# groundControl.net
KiCad netlist of a schematic drawn in EAGLE
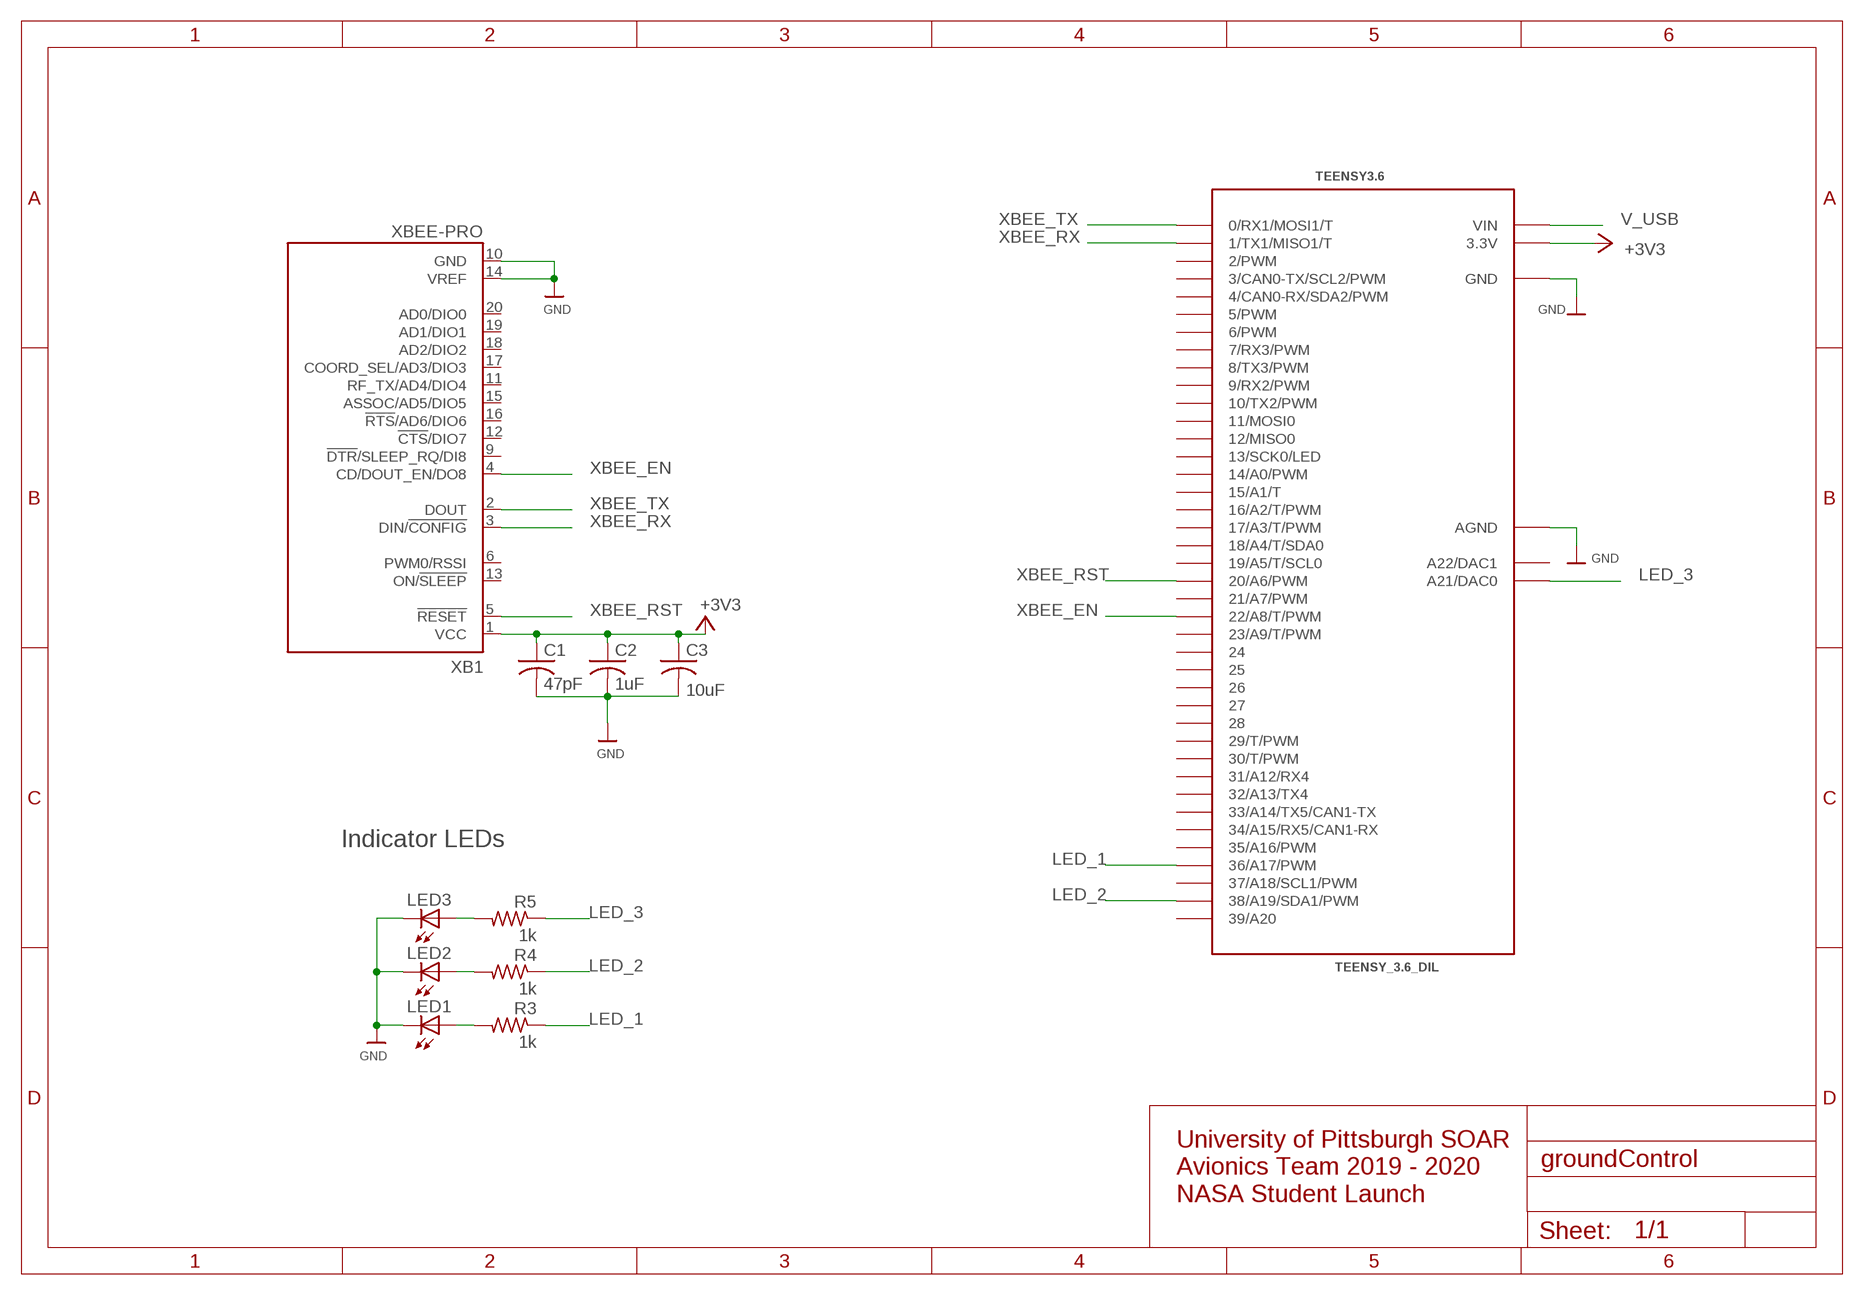
[diagram p0: schematic, sheet 1]

(export (version "E")
  (design (tool "Eeschema 10.0.6"))
  (components
    (comp (ref "C1")
      (value "47pF")
      (footprint "eagle-import:C025-040X050")
      (libsource (lib "eagle-import") (part "C-US025-040X050"))
    )
    (comp (ref "C2")
      (value "1uF")
      (footprint "eagle-import:C025-040X050")
      (libsource (lib "eagle-import") (part "C-US025-040X050"))
    )
    (comp (ref "C3")
      (value "10uF")
      (footprint "eagle-import:C025-040X050")
      (libsource (lib "eagle-import") (part "C-US025-040X050"))
    )
    (comp (ref "LED1")
      (value "LED3MM")
      (footprint "eagle-import:LED3MM")
      (libsource (lib "eagle-import") (part "LED3MM"))
    )
    (comp (ref "LED2")
      (value "LED3MM")
      (footprint "eagle-import:LED3MM")
      (libsource (lib "eagle-import") (part "LED3MM"))
    )
    (comp (ref "LED3")
      (value "LED3MM")
      (footprint "eagle-import:LED3MM")
      (libsource (lib "eagle-import") (part "LED3MM"))
    )
    (comp (ref "R3")
      (value "1k")
      (footprint "eagle-import:0309_10")
      (libsource (lib "eagle-import") (part "R-US_0309/10"))
    )
    (comp (ref "R4")
      (value "1k")
      (footprint "eagle-import:0309_10")
      (libsource (lib "eagle-import") (part "R-US_0309/10"))
    )
    (comp (ref "R5")
      (value "1k")
      (footprint "eagle-import:0309_10")
      (libsource (lib "eagle-import") (part "R-US_0309/10"))
    )
    (comp (ref "TEENSY3.6")
      (value "TEENSY_3.6_DIL")
      (footprint "eagle-import:TEENSY_3.6_DIL")
      (libsource (lib "eagle-import") (part "TEENSY_3.6_DIL"))
    )
    (comp (ref "XB1")
      (value "XBEE-PRO")
      (footprint "eagle-import:XBEE-PRO")
      (fields (field (name "MPN") "XBP24-AWI-001"))
      (libsource (lib "eagle-import") (part "XBEE-PRO"))
    )
  )
  (nets
    (net (code "1") (name "+3V3") (class "Default")
      (node (ref "C1") (pin "1") (pinfunction "1_1") (pintype "passive"))
      (node (ref "C2") (pin "1") (pinfunction "1_1") (pintype "passive"))
      (node (ref "C3") (pin "1") (pinfunction "1_1") (pintype "passive"))
      (node (ref "TEENSY3.6") (pin "3.3V") (pinfunction "3.3V_3.3V") (pintype "power_in"))
      (node (ref "TEENSY3.6") (pin "3.3V3") (pinfunction "3.3V_3.3V3") (pintype "power_in"))
      (node (ref "XB1") (pin "1") (pinfunction "VCC_1") (pintype "power_in"))
    )
    (net (code "2") (name "/LED_1") (class "Default")
      (node (ref "R3") (pin "1") (pinfunction "1_1") (pintype "passive"))
      (node (ref "TEENSY3.6") (pin "36/A17") (pinfunction "36/A17/PWM_36/A17") (pintype "bidirectional"))
    )
    (net (code "3") (name "/LED_2") (class "Default")
      (node (ref "R4") (pin "1") (pinfunction "1_1") (pintype "passive"))
      (node (ref "TEENSY3.6") (pin "38/A19") (pinfunction "38/A19/SDA1/PWM_38/A19") (pintype "bidirectional"))
    )
    (net (code "4") (name "/LED_3") (class "Default")
      (node (ref "R5") (pin "1") (pinfunction "1_1") (pintype "passive"))
      (node (ref "TEENSY3.6") (pin "A21") (pinfunction "A21/DAC0_A21") (pintype "bidirectional"))
    )
    (net (code "5") (name "/V_USB") (class "Default")
      (node (ref "TEENSY3.6") (pin "VIN") (pinfunction "VIN_VIN") (pintype "power_in"))
    )
    (net (code "6") (name "/XBEE_EN") (class "Default")
      (node (ref "TEENSY3.6") (pin "22/A8") (pinfunction "22/A8/T/PWM_22/A8") (pintype "bidirectional"))
      (node (ref "XB1") (pin "4") (pinfunction "CD/DOUT_EN/DO8_4") (pintype "output"))
    )
    (net (code "7") (name "/XBEE_RST") (class "Default")
      (node (ref "TEENSY3.6") (pin "20/A6") (pinfunction "20/A6/PWM_20/A6") (pintype "bidirectional"))
      (node (ref "XB1") (pin "5") (pinfunction "~{RESET}_5") (pintype "input"))
    )
    (net (code "8") (name "/XBEE_RX") (class "Default")
      (node (ref "TEENSY3.6") (pin "1") (pinfunction "1/TX1/MISO1/T_1") (pintype "bidirectional"))
      (node (ref "XB1") (pin "3") (pinfunction "DIN/~{CONFIG}_3") (pintype "input"))
    )
    (net (code "9") (name "/XBEE_TX") (class "Default")
      (node (ref "TEENSY3.6") (pin "0") (pinfunction "0/RX1/MOSI1/T_0") (pintype "bidirectional"))
      (node (ref "XB1") (pin "2") (pinfunction "DOUT_2") (pintype "output"))
    )
    (net (code "10") (name "GND") (class "Default")
      (node (ref "C1") (pin "2") (pinfunction "2_2") (pintype "passive"))
      (node (ref "C2") (pin "2") (pinfunction "2_2") (pintype "passive"))
      (node (ref "C3") (pin "2") (pinfunction "2_2") (pintype "passive"))
      (node (ref "LED1") (pin "K") (pinfunction "C_K") (pintype "passive"))
      (node (ref "LED2") (pin "K") (pinfunction "C_K") (pintype "passive"))
      (node (ref "LED3") (pin "K") (pinfunction "C_K") (pintype "passive"))
      (node (ref "TEENSY3.6") (pin "AGND") (pinfunction "AGND_AGND") (pintype "power_in"))
      (node (ref "TEENSY3.6") (pin "GND") (pinfunction "GND_GND") (pintype "power_in"))
      (node (ref "TEENSY3.6") (pin "GND1") (pinfunction "GND_GND1") (pintype "power_in"))
      (node (ref "XB1") (pin "10") (pinfunction "GND_10") (pintype "power_in"))
      (node (ref "XB1") (pin "14") (pinfunction "VREF_14") (pintype "input"))
    )
    (net (code "11") (name "Net-(LED1-PadA)") (class "Default")
      (node (ref "LED1") (pin "A") (pinfunction "A_A") (pintype "passive"))
      (node (ref "R3") (pin "2") (pinfunction "2_2") (pintype "passive"))
    )
    (net (code "12") (name "Net-(LED2-PadA)") (class "Default")
      (node (ref "LED2") (pin "A") (pinfunction "A_A") (pintype "passive"))
      (node (ref "R4") (pin "2") (pinfunction "2_2") (pintype "passive"))
    )
    (net (code "13") (name "Net-(LED3-PadA)") (class "Default")
      (node (ref "LED3") (pin "A") (pinfunction "A_A") (pintype "passive"))
      (node (ref "R5") (pin "2") (pinfunction "2_2") (pintype "passive"))
    )
    (net (code "14") (name "unconnected-(TEENSY3.6-2{slash}PWM-Pad2)") (class "Default")
      (node (ref "TEENSY3.6") (pin "2") (pinfunction "2/PWM_2") (pintype "bidirectional"))
    )
    (net (code "15") (name "unconnected-(TEENSY3.6-3{slash}CAN0-TX{slash}SCL2{slash}PWM-Pad3)") (class "Default")
      (node (ref "TEENSY3.6") (pin "3") (pinfunction "3/CAN0-TX/SCL2/PWM_3") (pintype "bidirectional"))
    )
    (net (code "16") (name "unconnected-(TEENSY3.6-4{slash}CAN0-RX{slash}SDA2{slash}PWM-Pad4)") (class "Default")
      (node (ref "TEENSY3.6") (pin "4") (pinfunction "4/CAN0-RX/SDA2/PWM_4") (pintype "bidirectional"))
    )
    (net (code "17") (name "unconnected-(TEENSY3.6-5{slash}PWM-Pad5)") (class "Default")
      (node (ref "TEENSY3.6") (pin "5") (pinfunction "5/PWM_5") (pintype "bidirectional"))
    )
    (net (code "18") (name "unconnected-(TEENSY3.6-6{slash}PWM-Pad6)") (class "Default")
      (node (ref "TEENSY3.6") (pin "6") (pinfunction "6/PWM_6") (pintype "bidirectional"))
    )
    (net (code "19") (name "unconnected-(TEENSY3.6-7{slash}RX3{slash}PWM-Pad7)") (class "Default")
      (node (ref "TEENSY3.6") (pin "7") (pinfunction "7/RX3/PWM_7") (pintype "bidirectional"))
    )
    (net (code "20") (name "unconnected-(TEENSY3.6-8{slash}TX3{slash}PWM-Pad8)") (class "Default")
      (node (ref "TEENSY3.6") (pin "8") (pinfunction "8/TX3/PWM_8") (pintype "bidirectional"))
    )
    (net (code "21") (name "unconnected-(TEENSY3.6-9{slash}RX2{slash}PWM-Pad9)") (class "Default")
      (node (ref "TEENSY3.6") (pin "9") (pinfunction "9/RX2/PWM_9") (pintype "bidirectional"))
    )
    (net (code "22") (name "unconnected-(TEENSY3.6-10{slash}TX2{slash}PWM-Pad10)") (class "Default")
      (node (ref "TEENSY3.6") (pin "10") (pinfunction "10/TX2/PWM_10") (pintype "bidirectional"))
    )
    (net (code "23") (name "unconnected-(TEENSY3.6-11{slash}MOSI0-Pad11)") (class "Default")
      (node (ref "TEENSY3.6") (pin "11") (pinfunction "11/MOSI0_11") (pintype "bidirectional"))
    )
    (net (code "24") (name "unconnected-(TEENSY3.6-12{slash}MISO0-Pad12)") (class "Default")
      (node (ref "TEENSY3.6") (pin "12") (pinfunction "12/MISO0_12") (pintype "bidirectional"))
    )
    (net (code "25") (name "unconnected-(TEENSY3.6-13{slash}SCK0{slash}LED-Pad13)") (class "Default")
      (node (ref "TEENSY3.6") (pin "13") (pinfunction "13/SCK0/LED_13") (pintype "bidirectional"))
    )
    (net (code "26") (name "unconnected-(TEENSY3.6-14{slash}A0{slash}PWM-Pad14{slash}A0)") (class "Default")
      (node (ref "TEENSY3.6") (pin "14/A0") (pinfunction "14/A0/PWM_14/A0") (pintype "bidirectional"))
    )
    (net (code "27") (name "unconnected-(TEENSY3.6-15{slash}A1{slash}T-Pad15{slash}A1)") (class "Default")
      (node (ref "TEENSY3.6") (pin "15/A1") (pinfunction "15/A1/T_15/A1") (pintype "bidirectional"))
    )
    (net (code "28") (name "unconnected-(TEENSY3.6-16{slash}A2{slash}T{slash}PWM-Pad16{slash}A2)") (class "Default")
      (node (ref "TEENSY3.6") (pin "16/A2") (pinfunction "16/A2/T/PWM_16/A2") (pintype "bidirectional"))
    )
    (net (code "29") (name "unconnected-(TEENSY3.6-17{slash}A3{slash}T{slash}PWM-Pad17{slash}A3)") (class "Default")
      (node (ref "TEENSY3.6") (pin "17/A3") (pinfunction "17/A3/T/PWM_17/A3") (pintype "bidirectional"))
    )
    (net (code "30") (name "unconnected-(TEENSY3.6-18{slash}A4{slash}T{slash}SDA0-Pad18{slash}A4)") (class "Default")
      (node (ref "TEENSY3.6") (pin "18/A4") (pinfunction "18/A4/T/SDA0_18/A4") (pintype "bidirectional"))
    )
    (net (code "31") (name "unconnected-(TEENSY3.6-19{slash}A5{slash}T{slash}SCL0-Pad19{slash}A5)") (class "Default")
      (node (ref "TEENSY3.6") (pin "19/A5") (pinfunction "19/A5/T/SCL0_19/A5") (pintype "bidirectional"))
    )
    (net (code "32") (name "unconnected-(TEENSY3.6-21{slash}A7{slash}PWM-Pad21{slash}A7)") (class "Default")
      (node (ref "TEENSY3.6") (pin "21/A7") (pinfunction "21/A7/PWM_21/A7") (pintype "bidirectional"))
    )
    (net (code "33") (name "unconnected-(TEENSY3.6-23{slash}A9{slash}T{slash}PWM-Pad23{slash}A9)") (class "Default")
      (node (ref "TEENSY3.6") (pin "23/A9") (pinfunction "23/A9/T/PWM_23/A9") (pintype "bidirectional"))
    )
    (net (code "34") (name "unconnected-(TEENSY3.6-29{slash}T{slash}PWM-Pad29)") (class "Default")
      (node (ref "TEENSY3.6") (pin "29") (pinfunction "29/T/PWM_29") (pintype "bidirectional"))
    )
    (net (code "35") (name "unconnected-(TEENSY3.6-30{slash}T{slash}PWM-Pad30)") (class "Default")
      (node (ref "TEENSY3.6") (pin "30") (pinfunction "30/T/PWM_30") (pintype "bidirectional"))
    )
    (net (code "36") (name "unconnected-(TEENSY3.6-31{slash}A12{slash}RX4-Pad31{slash}A12)") (class "Default")
      (node (ref "TEENSY3.6") (pin "31/A12") (pinfunction "31/A12/RX4_31/A12") (pintype "bidirectional"))
    )
    (net (code "37") (name "unconnected-(TEENSY3.6-32{slash}A13{slash}TX4-Pad32{slash}A13)") (class "Default")
      (node (ref "TEENSY3.6") (pin "32/A13") (pinfunction "32/A13/TX4_32/A13") (pintype "bidirectional"))
    )
    (net (code "38") (name "unconnected-(TEENSY3.6-33{slash}A14{slash}TX5{slash}CAN1-TX-Pad33{slash}A14)") (class "Default")
      (node (ref "TEENSY3.6") (pin "33/A14") (pinfunction "33/A14/TX5/CAN1-TX_33/A14") (pintype "bidirectional"))
    )
    (net (code "39") (name "unconnected-(TEENSY3.6-34{slash}A15{slash}RX5{slash}CAN1-RX-Pad34{slash}A15)") (class "Default")
      (node (ref "TEENSY3.6") (pin "34/A15") (pinfunction "34/A15/RX5/CAN1-RX_34/A15") (pintype "bidirectional"))
    )
    (net (code "40") (name "unconnected-(TEENSY3.6-35{slash}A16{slash}PWM-Pad35{slash}A16)") (class "Default")
      (node (ref "TEENSY3.6") (pin "35/A16") (pinfunction "35/A16/PWM_35/A16") (pintype "bidirectional"))
    )
    (net (code "41") (name "unconnected-(TEENSY3.6-37{slash}A18{slash}SCL1{slash}PWM-Pad37{slash}A18)") (class "Default")
      (node (ref "TEENSY3.6") (pin "37/A18") (pinfunction "37/A18/SCL1/PWM_37/A18") (pintype "bidirectional"))
    )
    (net (code "42") (name "unconnected-(TEENSY3.6-A22{slash}DAC1-PadA22)") (class "Default")
      (node (ref "TEENSY3.6") (pin "A22") (pinfunction "A22/DAC1_A22") (pintype "bidirectional"))
    )
    (net (code "43") (name "unconnected-(TEENSY3.6-Pad24)") (class "Default")
      (node (ref "TEENSY3.6") (pin "24") (pinfunction "24_24") (pintype "bidirectional"))
    )
    (net (code "44") (name "unconnected-(TEENSY3.6-Pad25)") (class "Default")
      (node (ref "TEENSY3.6") (pin "25") (pinfunction "25_25") (pintype "bidirectional"))
    )
    (net (code "45") (name "unconnected-(TEENSY3.6-Pad26)") (class "Default")
      (node (ref "TEENSY3.6") (pin "26") (pinfunction "26_26") (pintype "bidirectional"))
    )
    (net (code "46") (name "unconnected-(TEENSY3.6-Pad27)") (class "Default")
      (node (ref "TEENSY3.6") (pin "27") (pinfunction "27_27") (pintype "bidirectional"))
    )
    (net (code "47") (name "unconnected-(TEENSY3.6-Pad28)") (class "Default")
      (node (ref "TEENSY3.6") (pin "28") (pinfunction "28_28") (pintype "bidirectional"))
    )
    (net (code "48") (name "unconnected-(TEENSY3.6-Pad39{slash}A20)") (class "Default")
      (node (ref "TEENSY3.6") (pin "39/A20") (pinfunction "39/A20_39/A20") (pintype "bidirectional"))
    )
    (net (code "49") (name "unconnected-(XB1-AD0{slash}DIO0-Pad20)") (class "Default")
      (node (ref "XB1") (pin "20") (pinfunction "AD0/DIO0_20") (pintype "bidirectional"))
    )
    (net (code "50") (name "unconnected-(XB1-AD1{slash}DIO1-Pad19)") (class "Default")
      (node (ref "XB1") (pin "19") (pinfunction "AD1/DIO1_19") (pintype "bidirectional"))
    )
    (net (code "51") (name "unconnected-(XB1-AD2{slash}DIO2-Pad18)") (class "Default")
      (node (ref "XB1") (pin "18") (pinfunction "AD2/DIO2_18") (pintype "bidirectional"))
    )
    (net (code "52") (name "unconnected-(XB1-ASSOC{slash}AD5{slash}DIO5-Pad15)") (class "Default")
      (node (ref "XB1") (pin "15") (pinfunction "ASSOC/AD5/DIO5_15") (pintype "bidirectional"))
    )
    (net (code "53") (name "unconnected-(XB1-COORD_SEL{slash}AD3{slash}DIO3-Pad17)") (class "Default")
      (node (ref "XB1") (pin "17") (pinfunction "COORD_SEL/AD3/DIO3_17") (pintype "bidirectional"))
    )
    (net (code "54") (name "unconnected-(XB1-ON{slash}~{SLEEP}-Pad13)") (class "Default")
      (node (ref "XB1") (pin "13") (pinfunction "ON/~{SLEEP}_13") (pintype "output"))
    )
    (net (code "55") (name "unconnected-(XB1-PWM0{slash}RSSI-Pad6)") (class "Default")
      (node (ref "XB1") (pin "6") (pinfunction "PWM0/RSSI_6") (pintype "output"))
    )
    (net (code "56") (name "unconnected-(XB1-RF_TX{slash}AD4{slash}DIO4-Pad11)") (class "Default")
      (node (ref "XB1") (pin "11") (pinfunction "RF_TX/AD4/DIO4_11") (pintype "bidirectional"))
    )
    (net (code "57") (name "unconnected-(XB1-~{CTS}{slash}DIO7-Pad12)") (class "Default")
      (node (ref "XB1") (pin "12") (pinfunction "~{CTS}/DIO7_12") (pintype "bidirectional"))
    )
    (net (code "58") (name "unconnected-(XB1-~{DTR}{slash}SLEEP_RQ{slash}DI8-Pad9)") (class "Default")
      (node (ref "XB1") (pin "9") (pinfunction "~{DTR}/SLEEP_RQ/DI8_9") (pintype "bidirectional"))
    )
    (net (code "59") (name "unconnected-(XB1-~{RTS}{slash}AD6{slash}DIO6-Pad16)") (class "Default")
      (node (ref "XB1") (pin "16") (pinfunction "~{RTS}/AD6/DIO6_16") (pintype "bidirectional"))
    )
  )
)
